# ESP32_ADC_HUB.net
KiCad netlist of a schematic drawn in EAGLE
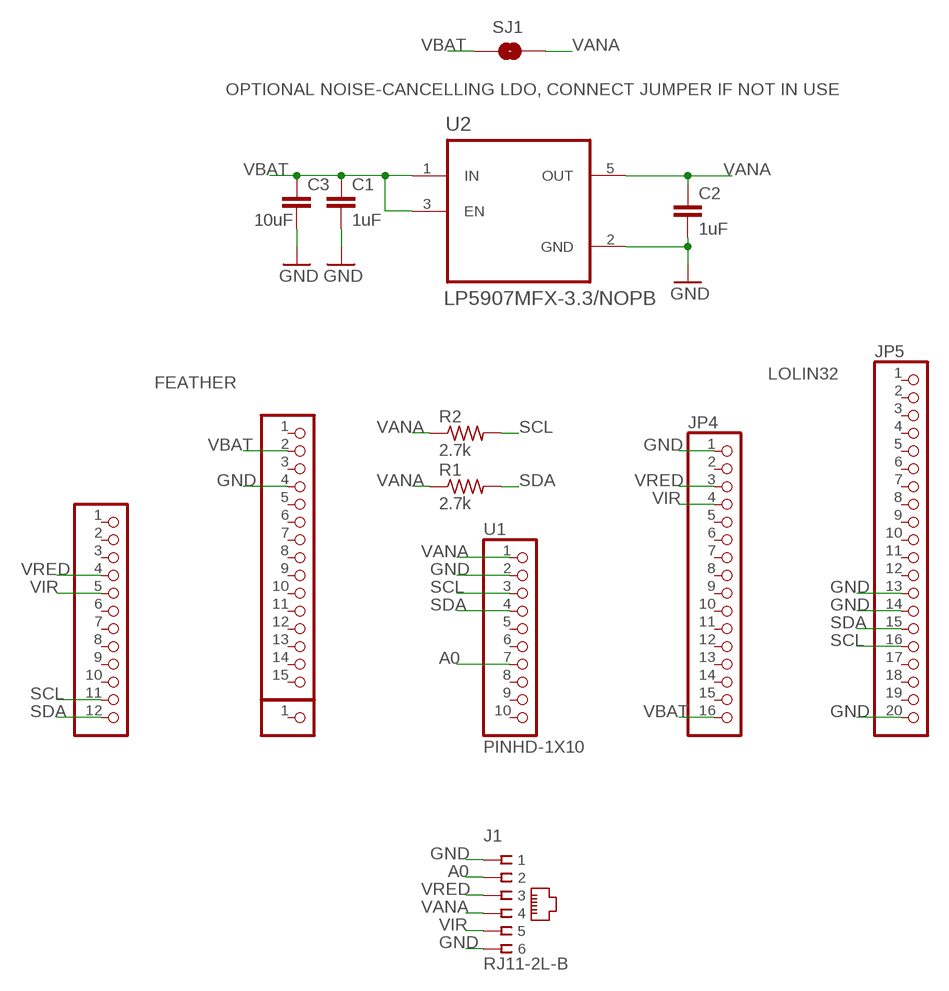
[diagram p0: schematic, sheet 1]

(export (version "E")
  (design (tool "Eeschema 10.0.6"))
  (components
    (comp (ref "C1")
      (value "1uF")
      (footprint "eagle-import:C050-024X044")
      (libsource (lib "eagle-import") (part "C-EU050-024X044"))
    )
    (comp (ref "C2")
      (value "1uF")
      (footprint "eagle-import:C050-024X044")
      (libsource (lib "eagle-import") (part "C-EU050-024X044"))
    )
    (comp (ref "C3")
      (value "10uF")
      (footprint "eagle-import:C050-024X044")
      (libsource (lib "eagle-import") (part "C-EU050-024X044"))
    )
    (comp (ref "J1")
      (value "RJ11-2L-B")
      (footprint "eagle-import:RJ11-NO_SHIELD")
      (fields (field (name "MF") "TYCO ELECTRONICS"))
      (libsource (lib "eagle-import") (part "RJ11-2L-B"))
    )
    (comp (ref "JP1")
      (value "PINHD-1X12-CB")
      (footprint "eagle-import:1X12-CB")
      (libsource (lib "eagle-import") (part "PINHD-1X12-CB"))
    )
    (comp (ref "JP2")
      (value "PINHD-1X15-CB")
      (footprint "eagle-import:1X15-CB")
      (libsource (lib "eagle-import") (part "PINHD-1X15-CB"))
    )
    (comp (ref "JP3")
      (value "PINHD-1X1CB")
      (footprint "eagle-import:1X01-CLEANBIG")
      (libsource (lib "eagle-import") (part "PINHD-1X1CB"))
    )
    (comp (ref "JP4")
      (value "PINHD-1X16")
      (footprint "eagle-import:1X16")
      (libsource (lib "eagle-import") (part "PINHD-1X16"))
    )
    (comp (ref "JP5")
      (value "PINHD-1X20")
      (footprint "eagle-import:1X20")
      (libsource (lib "eagle-import") (part "PINHD-1X20"))
    )
    (comp (ref "R1")
      (value "2.7k")
      (footprint "eagle-import:0204_7")
      (libsource (lib "eagle-import") (part "R-US_0204/7"))
    )
    (comp (ref "R2")
      (value "2.7k")
      (footprint "eagle-import:0204_7")
      (libsource (lib "eagle-import") (part "R-US_0204/7"))
    )
    (comp (ref "SJ1")
      (value "SOLDERJUMPERNC")
      (footprint "eagle-import:SJ_2S_SMALL")
      (libsource (lib "eagle-import") (part "SOLDERJUMPERNC"))
    )
    (comp (ref "U1")
      (value "PINHD-1X10")
      (footprint "eagle-import:1X10-BIG")
      (libsource (lib "eagle-import") (part "PINHD-1X10"))
    )
    (comp (ref "U2")
      (value "LP5907MFX-3.3/NOPB")
      (footprint "eagle-import:SOT95P280X145-5N")
      (fields (field (name "MF") "Texas Instruments"))
      (libsource (lib "eagle-import") (part "LP5907MFX-3.3/NOPB"))
    )
  )
  (nets
    (net (code "1") (name "/A0") (class "Default")
      (node (ref "J1") (pin "2") (pinfunction "2_2") (pintype "passive"))
      (node (ref "U1") (pin "7") (pinfunction "7_7") (pintype "passive"))
    )
    (net (code "2") (name "/SCL") (class "Default")
      (node (ref "JP1") (pin "11") (pinfunction "11_11") (pintype "passive"))
      (node (ref "JP5") (pin "16") (pinfunction "16_16") (pintype "passive"))
      (node (ref "R2") (pin "2") (pinfunction "2_2") (pintype "passive"))
      (node (ref "U1") (pin "3") (pinfunction "3_3") (pintype "passive"))
    )
    (net (code "3") (name "/SDA") (class "Default")
      (node (ref "JP1") (pin "12") (pinfunction "12_12") (pintype "passive"))
      (node (ref "JP5") (pin "15") (pinfunction "15_15") (pintype "passive"))
      (node (ref "R1") (pin "2") (pinfunction "2_2") (pintype "passive"))
      (node (ref "U1") (pin "4") (pinfunction "4_4") (pintype "passive"))
    )
    (net (code "4") (name "/VANA") (class "Default")
      (node (ref "C2") (pin "1") (pinfunction "1_1") (pintype "passive"))
      (node (ref "J1") (pin "4") (pinfunction "4_4") (pintype "passive"))
      (node (ref "R1") (pin "1") (pinfunction "1_1") (pintype "passive"))
      (node (ref "R2") (pin "1") (pinfunction "1_1") (pintype "passive"))
      (node (ref "SJ1") (pin "2") (pinfunction "2_2") (pintype "passive"))
      (node (ref "U1") (pin "1") (pinfunction "1_1") (pintype "passive"))
      (node (ref "U2") (pin "5") (pinfunction "OUT_5") (pintype "output"))
    )
    (net (code "5") (name "/VBAT") (class "Default")
      (node (ref "C1") (pin "1") (pinfunction "1_1") (pintype "passive"))
      (node (ref "C3") (pin "1") (pinfunction "1_1") (pintype "passive"))
      (node (ref "JP2") (pin "2") (pinfunction "2_2") (pintype "passive"))
      (node (ref "JP4") (pin "16") (pinfunction "16_16") (pintype "passive"))
      (node (ref "SJ1") (pin "1") (pinfunction "1_1") (pintype "passive"))
      (node (ref "U2") (pin "1") (pinfunction "IN_1") (pintype "input"))
      (node (ref "U2") (pin "3") (pinfunction "EN_3") (pintype "input"))
    )
    (net (code "6") (name "/VIR") (class "Default")
      (node (ref "J1") (pin "5") (pinfunction "5_5") (pintype "passive"))
      (node (ref "JP1") (pin "5") (pinfunction "5_5") (pintype "passive"))
      (node (ref "JP4") (pin "4") (pinfunction "4_4") (pintype "passive"))
    )
    (net (code "7") (name "/VRED") (class "Default")
      (node (ref "J1") (pin "3") (pinfunction "3_3") (pintype "passive"))
      (node (ref "JP1") (pin "4") (pinfunction "4_4") (pintype "passive"))
      (node (ref "JP4") (pin "3") (pinfunction "3_3") (pintype "passive"))
    )
    (net (code "8") (name "GND") (class "Default")
      (node (ref "C1") (pin "2") (pinfunction "2_2") (pintype "passive"))
      (node (ref "C2") (pin "2") (pinfunction "2_2") (pintype "passive"))
      (node (ref "C3") (pin "2") (pinfunction "2_2") (pintype "passive"))
      (node (ref "J1") (pin "1") (pinfunction "1_1") (pintype "passive"))
      (node (ref "J1") (pin "6") (pinfunction "6_6") (pintype "passive"))
      (node (ref "JP2") (pin "4") (pinfunction "4_4") (pintype "passive"))
      (node (ref "JP4") (pin "1") (pinfunction "1_1") (pintype "passive"))
      (node (ref "JP5") (pin "13") (pinfunction "13_13") (pintype "passive"))
      (node (ref "JP5") (pin "14") (pinfunction "14_14") (pintype "passive"))
      (node (ref "JP5") (pin "20") (pinfunction "20_20") (pintype "passive"))
      (node (ref "U1") (pin "2") (pinfunction "2_2") (pintype "passive"))
      (node (ref "U2") (pin "2") (pinfunction "GND_2") (pintype "power_in"))
    )
    (net (code "9") (name "unconnected-(JP1-Pad1)") (class "Default")
      (node (ref "JP1") (pin "1") (pinfunction "1_1") (pintype "passive"))
    )
    (net (code "10") (name "unconnected-(JP1-Pad2)") (class "Default")
      (node (ref "JP1") (pin "2") (pinfunction "2_2") (pintype "passive"))
    )
    (net (code "11") (name "unconnected-(JP1-Pad3)") (class "Default")
      (node (ref "JP1") (pin "3") (pinfunction "3_3") (pintype "passive"))
    )
    (net (code "12") (name "unconnected-(JP1-Pad6)") (class "Default")
      (node (ref "JP1") (pin "6") (pinfunction "6_6") (pintype "passive"))
    )
    (net (code "13") (name "unconnected-(JP1-Pad7)") (class "Default")
      (node (ref "JP1") (pin "7") (pinfunction "7_7") (pintype "passive"))
    )
    (net (code "14") (name "unconnected-(JP1-Pad8)") (class "Default")
      (node (ref "JP1") (pin "8") (pinfunction "8_8") (pintype "passive"))
    )
    (net (code "15") (name "unconnected-(JP1-Pad9)") (class "Default")
      (node (ref "JP1") (pin "9") (pinfunction "9_9") (pintype "passive"))
    )
    (net (code "16") (name "unconnected-(JP1-Pad10)") (class "Default")
      (node (ref "JP1") (pin "10") (pinfunction "10_10") (pintype "passive"))
    )
    (net (code "17") (name "unconnected-(JP2-Pad1)") (class "Default")
      (node (ref "JP2") (pin "1") (pinfunction "1_1") (pintype "passive"))
    )
    (net (code "18") (name "unconnected-(JP2-Pad3)") (class "Default")
      (node (ref "JP2") (pin "3") (pinfunction "3_3") (pintype "passive"))
    )
    (net (code "19") (name "unconnected-(JP2-Pad5)") (class "Default")
      (node (ref "JP2") (pin "5") (pinfunction "5_5") (pintype "passive"))
    )
    (net (code "20") (name "unconnected-(JP2-Pad6)") (class "Default")
      (node (ref "JP2") (pin "6") (pinfunction "6_6") (pintype "passive"))
    )
    (net (code "21") (name "unconnected-(JP2-Pad7)") (class "Default")
      (node (ref "JP2") (pin "7") (pinfunction "7_7") (pintype "passive"))
    )
    (net (code "22") (name "unconnected-(JP2-Pad8)") (class "Default")
      (node (ref "JP2") (pin "8") (pinfunction "8_8") (pintype "passive"))
    )
    (net (code "23") (name "unconnected-(JP2-Pad9)") (class "Default")
      (node (ref "JP2") (pin "9") (pinfunction "9_9") (pintype "passive"))
    )
    (net (code "24") (name "unconnected-(JP2-Pad10)") (class "Default")
      (node (ref "JP2") (pin "10") (pinfunction "10_10") (pintype "passive"))
    )
    (net (code "25") (name "unconnected-(JP2-Pad11)") (class "Default")
      (node (ref "JP2") (pin "11") (pinfunction "11_11") (pintype "passive"))
    )
    (net (code "26") (name "unconnected-(JP2-Pad12)") (class "Default")
      (node (ref "JP2") (pin "12") (pinfunction "12_12") (pintype "passive"))
    )
    (net (code "27") (name "unconnected-(JP2-Pad13)") (class "Default")
      (node (ref "JP2") (pin "13") (pinfunction "13_13") (pintype "passive"))
    )
    (net (code "28") (name "unconnected-(JP2-Pad14)") (class "Default")
      (node (ref "JP2") (pin "14") (pinfunction "14_14") (pintype "passive"))
    )
    (net (code "29") (name "unconnected-(JP2-Pad15)") (class "Default")
      (node (ref "JP2") (pin "15") (pinfunction "15_15") (pintype "passive"))
    )
    (net (code "30") (name "unconnected-(JP3-Pad1)") (class "Default")
      (node (ref "JP3") (pin "1") (pinfunction "1_1") (pintype "passive"))
    )
    (net (code "31") (name "unconnected-(JP4-Pad2)") (class "Default")
      (node (ref "JP4") (pin "2") (pinfunction "2_2") (pintype "passive"))
    )
    (net (code "32") (name "unconnected-(JP4-Pad5)") (class "Default")
      (node (ref "JP4") (pin "5") (pinfunction "5_5") (pintype "passive"))
    )
    (net (code "33") (name "unconnected-(JP4-Pad6)") (class "Default")
      (node (ref "JP4") (pin "6") (pinfunction "6_6") (pintype "passive"))
    )
    (net (code "34") (name "unconnected-(JP4-Pad7)") (class "Default")
      (node (ref "JP4") (pin "7") (pinfunction "7_7") (pintype "passive"))
    )
    (net (code "35") (name "unconnected-(JP4-Pad8)") (class "Default")
      (node (ref "JP4") (pin "8") (pinfunction "8_8") (pintype "passive"))
    )
    (net (code "36") (name "unconnected-(JP4-Pad9)") (class "Default")
      (node (ref "JP4") (pin "9") (pinfunction "9_9") (pintype "passive"))
    )
    (net (code "37") (name "unconnected-(JP4-Pad10)") (class "Default")
      (node (ref "JP4") (pin "10") (pinfunction "10_10") (pintype "passive"))
    )
    (net (code "38") (name "unconnected-(JP4-Pad11)") (class "Default")
      (node (ref "JP4") (pin "11") (pinfunction "11_11") (pintype "passive"))
    )
    (net (code "39") (name "unconnected-(JP4-Pad12)") (class "Default")
      (node (ref "JP4") (pin "12") (pinfunction "12_12") (pintype "passive"))
    )
    (net (code "40") (name "unconnected-(JP4-Pad13)") (class "Default")
      (node (ref "JP4") (pin "13") (pinfunction "13_13") (pintype "passive"))
    )
    (net (code "41") (name "unconnected-(JP4-Pad14)") (class "Default")
      (node (ref "JP4") (pin "14") (pinfunction "14_14") (pintype "passive"))
    )
    (net (code "42") (name "unconnected-(JP4-Pad15)") (class "Default")
      (node (ref "JP4") (pin "15") (pinfunction "15_15") (pintype "passive"))
    )
    (net (code "43") (name "unconnected-(JP5-Pad1)") (class "Default")
      (node (ref "JP5") (pin "1") (pinfunction "1_1") (pintype "passive"))
    )
    (net (code "44") (name "unconnected-(JP5-Pad2)") (class "Default")
      (node (ref "JP5") (pin "2") (pinfunction "2_2") (pintype "passive"))
    )
    (net (code "45") (name "unconnected-(JP5-Pad3)") (class "Default")
      (node (ref "JP5") (pin "3") (pinfunction "3_3") (pintype "passive"))
    )
    (net (code "46") (name "unconnected-(JP5-Pad4)") (class "Default")
      (node (ref "JP5") (pin "4") (pinfunction "4_4") (pintype "passive"))
    )
    (net (code "47") (name "unconnected-(JP5-Pad5)") (class "Default")
      (node (ref "JP5") (pin "5") (pinfunction "5_5") (pintype "passive"))
    )
    (net (code "48") (name "unconnected-(JP5-Pad6)") (class "Default")
      (node (ref "JP5") (pin "6") (pinfunction "6_6") (pintype "passive"))
    )
    (net (code "49") (name "unconnected-(JP5-Pad7)") (class "Default")
      (node (ref "JP5") (pin "7") (pinfunction "7_7") (pintype "passive"))
    )
    (net (code "50") (name "unconnected-(JP5-Pad8)") (class "Default")
      (node (ref "JP5") (pin "8") (pinfunction "8_8") (pintype "passive"))
    )
    (net (code "51") (name "unconnected-(JP5-Pad9)") (class "Default")
      (node (ref "JP5") (pin "9") (pinfunction "9_9") (pintype "passive"))
    )
    (net (code "52") (name "unconnected-(JP5-Pad10)") (class "Default")
      (node (ref "JP5") (pin "10") (pinfunction "10_10") (pintype "passive"))
    )
    (net (code "53") (name "unconnected-(JP5-Pad11)") (class "Default")
      (node (ref "JP5") (pin "11") (pinfunction "11_11") (pintype "passive"))
    )
    (net (code "54") (name "unconnected-(JP5-Pad12)") (class "Default")
      (node (ref "JP5") (pin "12") (pinfunction "12_12") (pintype "passive"))
    )
    (net (code "55") (name "unconnected-(JP5-Pad17)") (class "Default")
      (node (ref "JP5") (pin "17") (pinfunction "17_17") (pintype "passive"))
    )
    (net (code "56") (name "unconnected-(JP5-Pad18)") (class "Default")
      (node (ref "JP5") (pin "18") (pinfunction "18_18") (pintype "passive"))
    )
    (net (code "57") (name "unconnected-(JP5-Pad19)") (class "Default")
      (node (ref "JP5") (pin "19") (pinfunction "19_19") (pintype "passive"))
    )
    (net (code "58") (name "unconnected-(U1-Pad5)") (class "Default")
      (node (ref "U1") (pin "5") (pinfunction "5_5") (pintype "passive"))
    )
    (net (code "59") (name "unconnected-(U1-Pad6)") (class "Default")
      (node (ref "U1") (pin "6") (pinfunction "6_6") (pintype "passive"))
    )
    (net (code "60") (name "unconnected-(U1-Pad8)") (class "Default")
      (node (ref "U1") (pin "8") (pinfunction "8_8") (pintype "passive"))
    )
    (net (code "61") (name "unconnected-(U1-Pad9)") (class "Default")
      (node (ref "U1") (pin "9") (pinfunction "9_9") (pintype "passive"))
    )
    (net (code "62") (name "unconnected-(U1-Pad10)") (class "Default")
      (node (ref "U1") (pin "10") (pinfunction "10_10") (pintype "passive"))
    )
  )
)
